# MOTOR_WITH_LDR.net
KiCad netlist of a schematic drawn in EAGLE
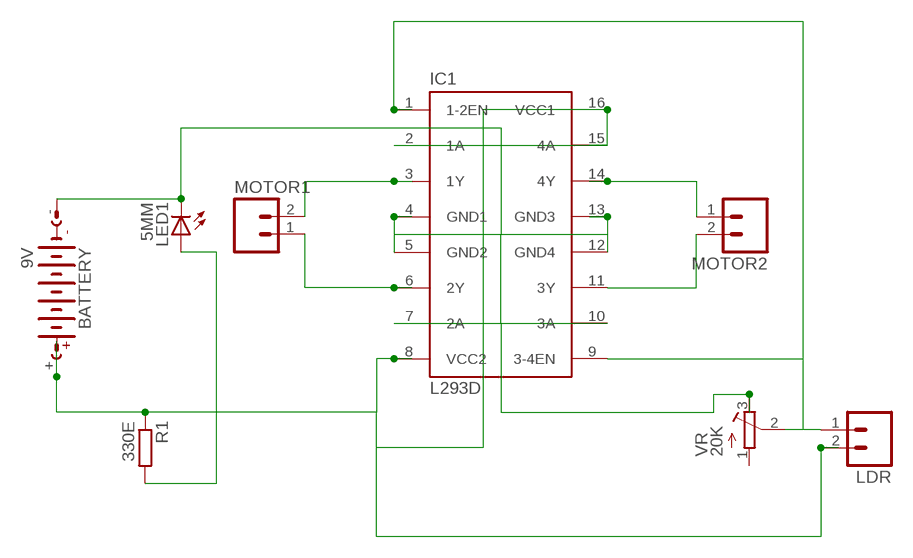
[diagram p0: schematic, sheet 1]

(export (version "E")
  (design (tool "Eeschema 10.0.6"))
  (components
    (comp (ref "BATTERY")
      (value "9V")
      (footprint "eagle-import:AB9V")
      (libsource (lib "eagle-import") (part "AB9V"))
    )
    (comp (ref "IC1")
      (value "L293D")
      (footprint "eagle-import:DIL16")
      (libsource (lib "eagle-import") (part "L293D"))
    )
    (comp (ref "LDR")
      (value "M02")
      (footprint "eagle-import:02P")
      (libsource (lib "eagle-import") (part "M02"))
    )
    (comp (ref "LED1")
      (value "5MM")
      (footprint "eagle-import:LED5MM")
      (libsource (lib "eagle-import") (part "LED5MM"))
    )
    (comp (ref "MOTOR1")
      (value "M02")
      (footprint "eagle-import:02P")
      (libsource (lib "eagle-import") (part "M02"))
    )
    (comp (ref "MOTOR2")
      (value "M02")
      (footprint "eagle-import:02P")
      (libsource (lib "eagle-import") (part "M02"))
    )
    (comp (ref "R1")
      (value "330E")
      (footprint "eagle-import:0204_7")
      (libsource (lib "eagle-import") (part "R-EU_0204/7"))
    )
    (comp (ref "VR")
      (value "20K")
      (footprint "eagle-import:RTRIM64P")
      (libsource (lib "eagle-import") (part "R-TRIMM64P"))
    )
  )
  (nets
    (net (code "1") (name "Net-(IC1-1-2EN)") (class "Default")
      (node (ref "IC1") (pin "1") (pinfunction "1-2EN_1") (pintype "input"))
      (node (ref "IC1") (pin "9") (pinfunction "3-4EN_9") (pintype "input"))
      (node (ref "LDR") (pin "1") (pinfunction "1_1") (pintype "passive"))
      (node (ref "VR") (pin "2") (pinfunction "S_2") (pintype "passive"))
    )
    (net (code "2") (name "Net-(IC1-1A)") (class "Default")
      (node (ref "BATTERY") (pin "+") (pinfunction "+_+") (pintype "passive"))
      (node (ref "IC1") (pin "15") (pinfunction "4A_15") (pintype "input"))
      (node (ref "IC1") (pin "16") (pinfunction "VCC1_16") (pintype "power_in"))
      (node (ref "IC1") (pin "2") (pinfunction "1A_2") (pintype "input"))
      (node (ref "IC1") (pin "8") (pinfunction "VCC2_8") (pintype "power_in"))
      (node (ref "LDR") (pin "2") (pinfunction "2_2") (pintype "passive"))
      (node (ref "R1") (pin "1") (pinfunction "1_1") (pintype "passive"))
    )
    (net (code "3") (name "Net-(IC1-1Y)") (class "Default")
      (node (ref "IC1") (pin "3") (pinfunction "1Y_3") (pintype "output"))
      (node (ref "MOTOR1") (pin "2") (pinfunction "2_2") (pintype "passive"))
    )
    (net (code "4") (name "Net-(IC1-2A)") (class "Default")
      (node (ref "BATTERY") (pin "-") (pinfunction "-_-") (pintype "passive"))
      (node (ref "IC1") (pin "10") (pinfunction "3A_10") (pintype "input"))
      (node (ref "IC1") (pin "12") (pinfunction "GND4_12") (pintype "power_in"))
      (node (ref "IC1") (pin "13") (pinfunction "GND3_13") (pintype "power_in"))
      (node (ref "IC1") (pin "4") (pinfunction "GND1_4") (pintype "power_in"))
      (node (ref "IC1") (pin "5") (pinfunction "GND2_5") (pintype "power_in"))
      (node (ref "IC1") (pin "7") (pinfunction "2A_7") (pintype "input"))
      (node (ref "LED1") (pin "K") (pinfunction "C_K") (pintype "passive"))
      (node (ref "VR") (pin "3") (pinfunction "A_3") (pintype "passive"))
    )
    (net (code "5") (name "Net-(IC1-2Y)") (class "Default")
      (node (ref "IC1") (pin "6") (pinfunction "2Y_6") (pintype "output"))
      (node (ref "MOTOR1") (pin "1") (pinfunction "1_1") (pintype "passive"))
    )
    (net (code "6") (name "Net-(IC1-3Y)") (class "Default")
      (node (ref "IC1") (pin "11") (pinfunction "3Y_11") (pintype "output"))
      (node (ref "MOTOR2") (pin "2") (pinfunction "2_2") (pintype "passive"))
    )
    (net (code "7") (name "Net-(IC1-4Y)") (class "Default")
      (node (ref "IC1") (pin "14") (pinfunction "4Y_14") (pintype "output"))
      (node (ref "MOTOR2") (pin "1") (pinfunction "1_1") (pintype "passive"))
    )
    (net (code "8") (name "Net-(LED1-PadA)") (class "Default")
      (node (ref "LED1") (pin "A") (pinfunction "A_A") (pintype "passive"))
      (node (ref "R1") (pin "2") (pinfunction "2_2") (pintype "passive"))
    )
    (net (code "9") (name "unconnected-(VR-E-Pad1)") (class "Default")
      (node (ref "VR") (pin "1") (pinfunction "E_1") (pintype "passive"))
    )
  )
)
